# PAW3-NOMAG_Cheesecake-Blueberry-LSM6DSV_.net
KiCad netlist of a schematic drawn in EasyEDA Pro
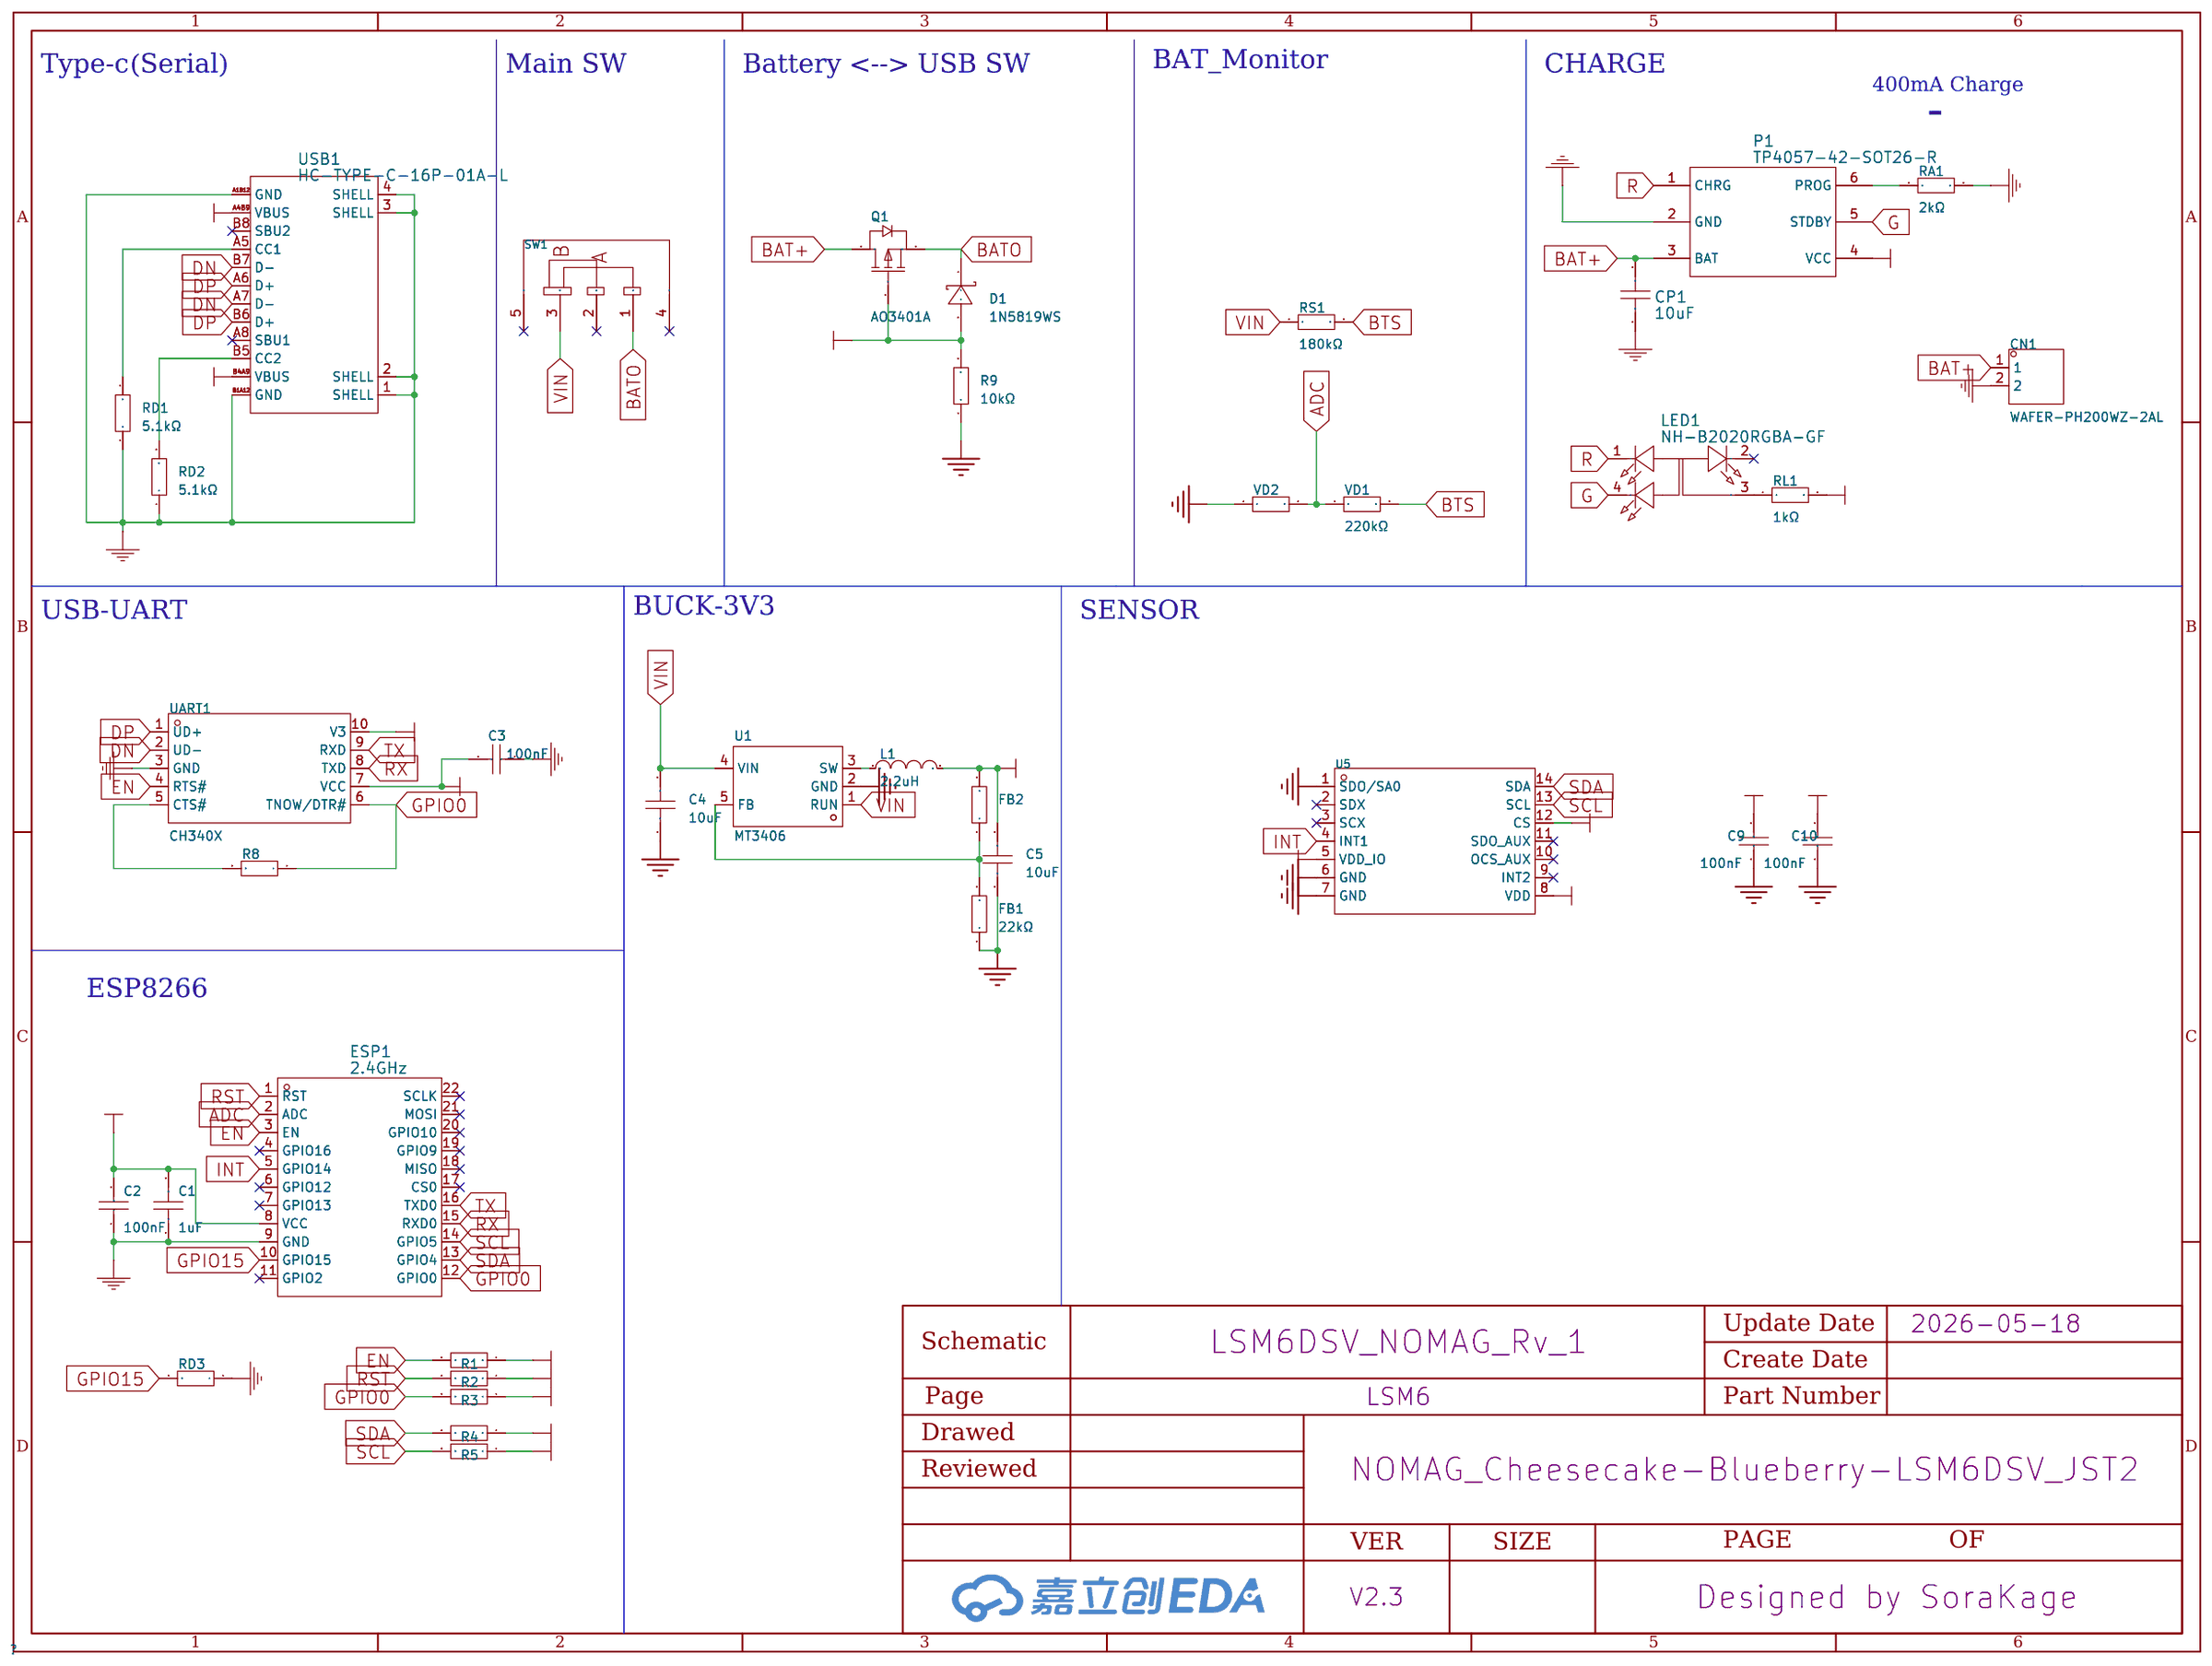
[diagram p0: schematic sheet]

(export (version "E")
  (design (tool "Eeschema 10.0.6"))
  (components
    (comp (ref "C1")
      (value "1uF")
      (footprint "easyedapro:C0402")
      (description "容值:1uF;精度:±10%;额定电压:25V;材质(温度系数):X5R;")
      (fields
        (field (name "Manufacturer Part") "CL05A105KA5NQNC")
        (field (name "Manufacturer") "SAMSUNG(三星)")
      )
      (libsource (lib "easyedapro") (part "CL05A105KA5NQNC"))
    )
    (comp (ref "C2")
      (value "100nF")
      (footprint "easyedapro:C0402")
      (description "容值:100nF;精度:±10%;额定电压:16V;材质(温度系数):X7R;")
      (fields
        (field (name "Manufacturer Part") "CL05B104KO5NNNC")
        (field (name "Manufacturer") "SAMSUNG(三星)")
      )
      (libsource (lib "easyedapro") (part "CL05B104KO5NNNC"))
    )
    (comp (ref "C3")
      (value "100nF")
      (footprint "easyedapro:C0402")
      (description "容值:100nF;精度:±10%;额定电压:16V;材质(温度系数):X7R;")
      (fields
        (field (name "Manufacturer Part") "CL05B104KO5NNNC")
        (field (name "Manufacturer") "SAMSUNG(三星)")
      )
      (libsource (lib "easyedapro") (part "CL05B104KO5NNNC"))
    )
    (comp (ref "C4")
      (value "10uF")
      (footprint "easyedapro:C0603")
      (description "容值:10uF;精度:±10%;额定电压:10V;材质(温度系数):X5R;")
      (fields
        (field (name "Manufacturer Part") "CL10A106KP8NNNC")
        (field (name "Manufacturer") "SAMSUNG(三星)")
      )
      (libsource (lib "easyedapro") (part "CL10A106KP8NNNC"))
    )
    (comp (ref "C5")
      (value "10uF")
      (footprint "easyedapro:C0603")
      (description "容值:10uF;精度:±10%;额定电压:10V;材质(温度系数):X5R;")
      (fields
        (field (name "Manufacturer Part") "CL10A106KP8NNNC")
        (field (name "Manufacturer") "SAMSUNG(三星)")
      )
      (libsource (lib "easyedapro") (part "CL10A106KP8NNNC"))
    )
    (comp (ref "C9")
      (value "100nF")
      (footprint "easyedapro:C0402")
      (description "容值:100nF;精度:±10%;额定电压:16V;材质(温度系数):X7R;")
      (fields
        (field (name "Manufacturer Part") "CL05B104KO5NNNC")
        (field (name "Manufacturer") "SAMSUNG(三星)")
      )
      (libsource (lib "easyedapro") (part "CL05B104KO5NNNC"))
    )
    (comp (ref "C10")
      (value "100nF")
      (footprint "easyedapro:C0402")
      (description "容值:100nF;精度:±10%;额定电压:16V;材质(温度系数):X7R;")
      (fields
        (field (name "Manufacturer Part") "CL05B104KO5NNNC")
        (field (name "Manufacturer") "SAMSUNG(三星)")
      )
      (libsource (lib "easyedapro") (part "CL05B104KO5NNNC"))
    )
    (comp (ref "CN1")
      (value "WAFER-PH200WZ-2AL")
      (footprint "easyedapro:CONN-TH_S2B-PH-K-S-LF-SN")
      (description "插针结构:1x2P;间距:2mm;安装方式:弯插;参考系列:PH;总PIN数:2P;排数:1;每排PIN数:2;行距:-;触头材质:黄铜;")
      (fields (field (name "Manufacturer") "HANBO(汉博)"))
      (libsource (lib "easyedapro") (part "S2B-PH-K-S(LF)(SN)"))
    )
    (comp (ref "CP1")
      (value "10uF")
      (footprint "easyedapro:C0603")
      (fields
        (field (name "Manufacturer Part") "CL10A106KP8NNNC")
        (field (name "Manufacturer") "SAMSUNG(三星)")
      )
      (libsource (lib "easyedapro") (part "10uF"))
    )
    (comp (ref "D1")
      (value "1N5819WS")
      (footprint "easyedapro:SOD-323_L1.8-W1.3-LS2.5-RD")
      (description "直流反向耐压(Vr):40V;平均整流电流(Io):1A;正向压降(Vf):600mV@1A;")
      (fields (field (name "Manufacturer") "Hottech(合科泰)"))
      (libsource (lib "easyedapro") (part "1N5819WS"))
    )
    (comp (ref "ESP1")
      (value "2.4GHz")
      (description "核心处理器:ESP8266芯片;频率:2.4GHz;天线形式:板载PCB天线;发射功率:16dBm;接收灵敏度:-90dBm;")
      (fields
        (field (name "Manufacturer Part") "ESP-12F(ESP8266MOD)")
        (field (name "Manufacturer") "Ai-Thinker(安信可)")
      )
      (libsource (lib "easyedapro") (part "ESP-12F(ESP8266MOD)"))
    )
    (comp (ref "FB1")
      (value "22kΩ")
      (footprint "easyedapro:R0402")
      (description "电阻类型:厚膜电阻;阻值:22kΩ;精度:±1%;功率:62.5mW;")
      (fields
        (field (name "Manufacturer Part") "0402WGF2202TCE")
        (field (name "Manufacturer") "UNI-ROYAL(厚声)")
      )
      (libsource (lib "easyedapro") (part "0402WGF2202TCE"))
    )
    (comp (ref "FB2")
      (value "100kΩ")
      (footprint "easyedapro:R0402")
      (fields
        (field (name "Manufacturer Part") "0402WGF1003TCE")
        (field (name "Manufacturer") "UNI-ROYAL(厚声)")
      )
      (libsource (lib "easyedapro") (part "0402WGF1003TCE"))
    )
    (comp (ref "L1")
      (value "2.2uH")
      (footprint "easyedapro:IND-SMD_L2.5-W2.0_YXMBL252010P")
      (description "类型:一体成型电感;电感值:2.2uH;精度:±20%;额定电流:2.1A;饱和电流(Isat):3A;")
      (fields (field (name "Manufacturer Part") "APH252010T2R2M") (field (name "Manufacturer") "APV(爱普微)"))
      (libsource (lib "easyedapro") (part "APH252010T2R2M"))
    )
    (comp (ref "LED1")
      (value "NH-B2020RGBA-GF")
      (footprint "easyedapro:LED-ARRAY-SMD_4P-L2.1-W2.1-TL_NH-B2020RGBA")
      (fields (field (name "Manufacturer") "国星光电"))
      (libsource (lib "easyedapro") (part "NH-B2020RGBA-GF"))
    )
    (comp (ref "P1")
      (value "TP4057-42-SOT26-R")
      (footprint "easyedapro:SOT-23-6_L2.9-W1.6-P0.95-LS2.8-BL")
      (fields (field (name "Manufacturer") "TOPPOWER(南京拓微)"))
      (libsource (lib "easyedapro") (part "TP4057"))
    )
    (comp (ref "Q1")
      (value "AO3401A")
      (footprint "easyedapro:SOT-23_L2.9-W1.3-P1.90-LS2.4-BR")
      (description "类型:P沟道;漏源电压(Vdss):30V;连续漏极电流(Id):4A;功率(Pd):1.4W;导通电阻(RDS(on)@Vgs,Id):44mΩ@10V,4.3A;")
      (fields (field (name "Manufacturer") "AOS"))
      (libsource (lib "easyedapro") (part "AO3401A"))
    )
    (comp (ref "R1")
      (value "4.7kΩ")
      (footprint "easyedapro:R0402")
      (fields
        (field (name "Manufacturer Part") "0402WGF4701TCE")
        (field (name "Manufacturer") "UNI-ROYAL(厚声)")
      )
      (libsource (lib "easyedapro") (part "0402WGF4701TCE"))
    )
    (comp (ref "R2")
      (value "4.7kΩ")
      (footprint "easyedapro:R0402")
      (fields
        (field (name "Manufacturer Part") "0402WGF4701TCE")
        (field (name "Manufacturer") "UNI-ROYAL(厚声)")
      )
      (libsource (lib "easyedapro") (part "0402WGF4701TCE"))
    )
    (comp (ref "R3")
      (value "4.7kΩ")
      (footprint "easyedapro:R0402")
      (fields
        (field (name "Manufacturer Part") "0402WGF4701TCE")
        (field (name "Manufacturer") "UNI-ROYAL(厚声)")
      )
      (libsource (lib "easyedapro") (part "0402WGF4701TCE"))
    )
    (comp (ref "R4")
      (value "4.7kΩ")
      (footprint "easyedapro:R0402")
      (fields
        (field (name "Manufacturer Part") "0402WGF4701TCE")
        (field (name "Manufacturer") "UNI-ROYAL(厚声)")
      )
      (libsource (lib "easyedapro") (part "0402WGF4701TCE"))
    )
    (comp (ref "R5")
      (value "4.7kΩ")
      (footprint "easyedapro:R0402")
      (fields
        (field (name "Manufacturer Part") "0402WGF4701TCE")
        (field (name "Manufacturer") "UNI-ROYAL(厚声)")
      )
      (libsource (lib "easyedapro") (part "0402WGF4701TCE"))
    )
    (comp (ref "R8")
      (value "4.7kΩ")
      (footprint "easyedapro:R0402")
      (fields
        (field (name "Manufacturer Part") "0402WGF4701TCE")
        (field (name "Manufacturer") "UNI-ROYAL(厚声)")
      )
      (libsource (lib "easyedapro") (part "0402WGF4701TCE"))
    )
    (comp (ref "R9")
      (value "10kΩ")
      (footprint "easyedapro:R0402")
      (description "电阻类型:厚膜电阻;阻值:10kΩ;精度:±1%;功率:62.5mW;")
      (fields
        (field (name "Manufacturer Part") "0402WGF1002TCE")
        (field (name "Manufacturer") "UNI-ROYAL(厚声)")
      )
      (libsource (lib "easyedapro") (part "0402WGF1002TCE"))
    )
    (comp (ref "RA1")
      (value "2kΩ")
      (footprint "easyedapro:R0402")
      (description "电阻类型:厚膜电阻;阻值:2kΩ;精度:±1%;功率:62.5mW;")
      (fields
        (field (name "Manufacturer Part") "0402WGF2001TCE")
        (field (name "Manufacturer") "UNI-ROYAL(厚声)")
      )
      (libsource (lib "easyedapro") (part "0402WGF2001TCE"))
    )
    (comp (ref "RD1")
      (value "5.1kΩ")
      (footprint "easyedapro:R0402")
      (description "电阻类型:厚膜电阻;阻值:5.1kΩ;精度:±1%;功率:62.5mW;")
      (fields
        (field (name "Manufacturer Part") "0402WGF5101TCE")
        (field (name "Manufacturer") "UNI-ROYAL(厚声)")
      )
      (libsource (lib "easyedapro") (part "0402WGF5101TCE"))
    )
    (comp (ref "RD2")
      (value "5.1kΩ")
      (footprint "easyedapro:R0402")
      (description "电阻类型:厚膜电阻;阻值:5.1kΩ;精度:±1%;功率:62.5mW;")
      (fields
        (field (name "Manufacturer Part") "0402WGF5101TCE")
        (field (name "Manufacturer") "UNI-ROYAL(厚声)")
      )
      (libsource (lib "easyedapro") (part "0402WGF5101TCE"))
    )
    (comp (ref "RD3")
      (value "4.7kΩ")
      (footprint "easyedapro:R0402")
      (fields
        (field (name "Manufacturer Part") "0402WGF4701TCE")
        (field (name "Manufacturer") "UNI-ROYAL(厚声)")
      )
      (libsource (lib "easyedapro") (part "0402WGF4701TCE"))
    )
    (comp (ref "RL1")
      (value "1kΩ")
      (footprint "easyedapro:R0402")
      (description "电阻类型:厚膜电阻;阻值:1kΩ;精度:±1%;功率:62.5mW;")
      (fields
        (field (name "Manufacturer Part") "0402WGF1001TCE")
        (field (name "Manufacturer") "UNI-ROYAL(厚声)")
      )
      (libsource (lib "easyedapro") (part "0402WGF1001TCE"))
    )
    (comp (ref "RS1")
      (value "180kΩ")
      (footprint "easyedapro:R0402")
      (description "阻值:180kΩ;精度:±1%;功率:62.5mW;温度系数:±100ppm/°C;电阻类型:厚膜电阻;")
      (fields
        (field (name "Manufacturer Part") "0402WGF1803TCE")
        (field (name "Manufacturer") "UNI-ROYAL(厚声)")
      )
      (libsource (lib "easyedapro") (part "0402WGF1803TCE"))
    )
    (comp (ref "SW1")
      (value "K3-1270S-F2")
      (footprint "easyedapro:SW-TH_K3-1270S-F2")
      (fields (field (name "Manufacturer") "韩国韩荣"))
      (libsource (lib "easyedapro") (part "K3-1270S-F2"))
    )
    (comp (ref "U1")
      (value "MT3406")
      (footprint "easyedapro:SOT-23-5_L3.0-W1.7-P0.95-LS2.8-BR")
      (description "功能类型:降压型;同步整流:-;输出通道数:-;拓扑结构:-;输入电压:-;输出电流(最大值):-;开关频率:-;")
      (fields (field (name "Manufacturer") "西安航天民芯"))
      (libsource (lib "easyedapro") (part "M3406"))
    )
    (comp (ref "U5")
      (value "LSM6DSVQTR")
      (footprint "easyedapro:LGA-14_L3.0-W2.5-P0.50-TL")
      (fields (field (name "Manufacturer") "ST(意法半导体)"))
      (libsource (lib "easyedapro") (part "LSM6DSVQTR"))
    )
    (comp (ref "UART1")
      (value "CH340X")
      (footprint "easyedapro:MSOP-10_L3.0-W3.0-P0.50-LS5.0-BL")
      (fields (field (name "Manufacturer") "WCH(南京沁恒)"))
      (libsource (lib "easyedapro") (part "CH340X"))
    )
    (comp (ref "USB1")
      (value "HC-TYPE-C-16P-01A-L")
      (footprint "easyedapro:USB-C-SMD_G-SWITCH_GT-USB-7010EN")
      (fields (field (name "Manufacturer") "HCTL(华灿天禄)"))
      (libsource (lib "easyedapro") (part "HC-TYPE-C-16P-01A-L"))
    )
    (comp (ref "VD1")
      (value "220kΩ")
      (footprint "easyedapro:R0402")
      (description "电阻类型:厚膜电阻;阻值:220kΩ;精度:±1%;功率:62.5mW;")
      (fields
        (field (name "Manufacturer Part") "0402WGF2203TCE")
        (field (name "Manufacturer") "UNI-ROYAL(厚声)")
      )
      (libsource (lib "easyedapro") (part "0402WGF2203TCE"))
    )
    (comp (ref "VD2")
      (value "100kΩ")
      (footprint "easyedapro:R0402")
      (fields
        (field (name "Manufacturer Part") "0402WGF1003TCE")
        (field (name "Manufacturer") "UNI-ROYAL(厚声)")
      )
      (libsource (lib "easyedapro") (part "0402WGF1003TCE"))
    )
  )
  (nets
    (net (code "1") (name "+5V") (class "Default")
      (node (ref "D1") (pin "2") (pinfunction "A_2") (pintype "unspecified"))
      (node (ref "P1") (pin "4") (pinfunction "VCC_4") (pintype "unspecified"))
      (node (ref "Q1") (pin "1") (pinfunction "G_1") (pintype "input"))
      (node (ref "R9") (pin "2") (pinfunction "2_2") (pintype "input"))
      (node (ref "RL1") (pin "2") (pinfunction "2_2") (pintype "input"))
      (node (ref "USB1") (pin "A4B9") (pinfunction "VBUS_A4B9") (pintype "unspecified"))
      (node (ref "USB1") (pin "B4A9") (pinfunction "VBUS_B4A9") (pintype "unspecified"))
    )
    (net (code "2") (name "3V3") (class "Default")
      (node (ref "C1") (pin "2") (pinfunction "2_2") (pintype "unspecified"))
      (node (ref "C10") (pin "1") (pinfunction "1_1") (pintype "input"))
      (node (ref "C2") (pin "2") (pinfunction "2_2") (pintype "input"))
      (node (ref "C3") (pin "2") (pinfunction "2_2") (pintype "input"))
      (node (ref "C5") (pin "2") (pinfunction "2_2") (pintype "unspecified"))
      (node (ref "C9") (pin "1") (pinfunction "1_1") (pintype "input"))
      (node (ref "ESP1") (pin "8") (pinfunction "VCC_8") (pintype "input"))
      (node (ref "FB2") (pin "2") (pinfunction "2_2") (pintype "input"))
      (node (ref "L1") (pin "2") (pinfunction "2_2") (pintype "unspecified"))
      (node (ref "R1") (pin "1") (pinfunction "1_1") (pintype "input"))
      (node (ref "R2") (pin "1") (pinfunction "1_1") (pintype "input"))
      (node (ref "R3") (pin "1") (pinfunction "1_1") (pintype "input"))
      (node (ref "R4") (pin "1") (pinfunction "1_1") (pintype "input"))
      (node (ref "R5") (pin "1") (pinfunction "1_1") (pintype "input"))
      (node (ref "U5") (pin "12") (pinfunction "CS_12") (pintype "unspecified"))
      (node (ref "U5") (pin "5") (pinfunction "VDD_IO_5") (pintype "unspecified"))
      (node (ref "U5") (pin "8") (pinfunction "VDD_8") (pintype "unspecified"))
      (node (ref "UART1") (pin "10") (pinfunction "V3_10") (pintype "unspecified"))
      (node (ref "UART1") (pin "7") (pinfunction "VCC_7") (pintype "unspecified"))
    )
    (net (code "3") (name "ADC") (class "Default")
      (node (ref "ESP1") (pin "2") (pinfunction "ADC_2") (pintype "input"))
      (node (ref "VD1") (pin "1") (pinfunction "1_1") (pintype "input"))
      (node (ref "VD2") (pin "2") (pinfunction "2_2") (pintype "input"))
    )
    (net (code "4") (name "BAT+") (class "Default")
      (node (ref "CN1") (pin "1") (pinfunction "1_1") (pintype "unspecified"))
      (node (ref "CP1") (pin "2") (pinfunction "2_2") (pintype "input"))
      (node (ref "P1") (pin "3") (pinfunction "BAT_3") (pintype "unspecified"))
      (node (ref "Q1") (pin "3") (pinfunction "D_3") (pintype "input"))
    )
    (net (code "5") (name "BATO") (class "Default")
      (node (ref "D1") (pin "1") (pinfunction "K_1") (pintype "unspecified"))
      (node (ref "Q1") (pin "2") (pinfunction "S_2") (pintype "input"))
      (node (ref "SW1") (pin "1") (pinfunction "1_1") (pintype "input"))
    )
    (net (code "6") (name "BTS") (class "Default")
      (node (ref "RS1") (pin "2") (pinfunction "2_2") (pintype "input"))
      (node (ref "VD1") (pin "2") (pinfunction "2_2") (pintype "input"))
    )
    (net (code "7") (name "DN") (class "Default")
      (node (ref "UART1") (pin "2") (pinfunction "UD-_2") (pintype "unspecified"))
      (node (ref "USB1") (pin "A7") (pinfunction "D-_A7") (pintype "unspecified"))
      (node (ref "USB1") (pin "B7") (pinfunction "D-_B7") (pintype "unspecified"))
    )
    (net (code "8") (name "DP") (class "Default")
      (node (ref "UART1") (pin "1") (pinfunction "UD+_1") (pintype "unspecified"))
      (node (ref "USB1") (pin "A6") (pinfunction "D+_A6") (pintype "unspecified"))
      (node (ref "USB1") (pin "B6") (pinfunction "D+_B6") (pintype "unspecified"))
    )
    (net (code "9") (name "EN") (class "Default")
      (node (ref "ESP1") (pin "3") (pinfunction "EN_3") (pintype "input"))
      (node (ref "R1") (pin "2") (pinfunction "2_2") (pintype "input"))
      (node (ref "UART1") (pin "4") (pinfunction "RTS#_4") (pintype "unspecified"))
    )
    (net (code "10") (name "G") (class "Default")
      (node (ref "LED1") (pin "4") (pinfunction "-_4") (pintype "unspecified"))
      (node (ref "P1") (pin "5") (pinfunction "STDBY_5") (pintype "unspecified"))
    )
    (net (code "11") (name "GND") (class "Default")
      (node (ref "C1") (pin "1") (pinfunction "1_1") (pintype "unspecified"))
      (node (ref "C10") (pin "2") (pinfunction "2_2") (pintype "input"))
      (node (ref "C2") (pin "1") (pinfunction "1_1") (pintype "input"))
      (node (ref "C3") (pin "1") (pinfunction "1_1") (pintype "input"))
      (node (ref "C4") (pin "1") (pinfunction "1_1") (pintype "unspecified"))
      (node (ref "C5") (pin "1") (pinfunction "1_1") (pintype "unspecified"))
      (node (ref "C9") (pin "2") (pinfunction "2_2") (pintype "input"))
      (node (ref "CN1") (pin "2") (pinfunction "2_2") (pintype "unspecified"))
      (node (ref "CP1") (pin "1") (pinfunction "1_1") (pintype "input"))
      (node (ref "ESP1") (pin "9") (pinfunction "GND_9") (pintype "input"))
      (node (ref "FB1") (pin "1") (pinfunction "1_1") (pintype "input"))
      (node (ref "P1") (pin "2") (pinfunction "GND_2") (pintype "unspecified"))
      (node (ref "R9") (pin "1") (pinfunction "1_1") (pintype "input"))
      (node (ref "RA1") (pin "2") (pinfunction "2_2") (pintype "input"))
      (node (ref "RD1") (pin "1") (pinfunction "1_1") (pintype "input"))
      (node (ref "RD2") (pin "1") (pinfunction "1_1") (pintype "input"))
      (node (ref "RD3") (pin "1") (pinfunction "1_1") (pintype "input"))
      (node (ref "U1") (pin "2") (pinfunction "GND_2") (pintype "input"))
      (node (ref "U5") (pin "1") (pinfunction "SDO/SA0_1") (pintype "unspecified"))
      (node (ref "U5") (pin "6") (pinfunction "GND_6") (pintype "unspecified"))
      (node (ref "U5") (pin "7") (pinfunction "GND_7") (pintype "unspecified"))
      (node (ref "UART1") (pin "3") (pinfunction "GND_3") (pintype "unspecified"))
      (node (ref "USB1") (pin "1") (pinfunction "SHELL_1") (pintype "unspecified"))
      (node (ref "USB1") (pin "2") (pinfunction "SHELL_2") (pintype "unspecified"))
      (node (ref "USB1") (pin "3") (pinfunction "SHELL_3") (pintype "unspecified"))
      (node (ref "USB1") (pin "4") (pinfunction "SHELL_4") (pintype "unspecified"))
      (node (ref "USB1") (pin "A1B12") (pinfunction "GND_A1B12") (pintype "unspecified"))
      (node (ref "USB1") (pin "B1A12") (pinfunction "GND_B1A12") (pintype "unspecified"))
      (node (ref "VD2") (pin "1") (pinfunction "1_1") (pintype "input"))
    )
    (net (code "12") (name "GPIO0") (class "Default")
      (node (ref "ESP1") (pin "12") (pinfunction "GPIO0_12") (pintype "input"))
      (node (ref "R3") (pin "2") (pinfunction "2_2") (pintype "input"))
      (node (ref "R8") (pin "1") (pinfunction "1_1") (pintype "input"))
      (node (ref "UART1") (pin "6") (pinfunction "TNOW/DTR#_6") (pintype "unspecified"))
    )
    (net (code "13") (name "GPIO15") (class "Default")
      (node (ref "ESP1") (pin "10") (pinfunction "GPIO15_10") (pintype "input"))
      (node (ref "RD3") (pin "2") (pinfunction "2_2") (pintype "input"))
    )
    (net (code "14") (name "INT") (class "Default")
      (node (ref "ESP1") (pin "5") (pinfunction "GPIO14_5") (pintype "input"))
      (node (ref "U5") (pin "4") (pinfunction "INT1_4") (pintype "unspecified"))
    )
    (net (code "15") (name "Net-(LED1-+)") (class "Default")
      (node (ref "LED1") (pin "3") (pinfunction "+_3") (pintype "unspecified"))
      (node (ref "RL1") (pin "1") (pinfunction "1_1") (pintype "input"))
    )
    (net (code "16") (name "Net-(P1-PROG)") (class "Default")
      (node (ref "P1") (pin "6") (pinfunction "PROG_6") (pintype "unspecified"))
      (node (ref "RA1") (pin "1") (pinfunction "1_1") (pintype "input"))
    )
    (net (code "17") (name "Net-(U1-FB)") (class "Default")
      (node (ref "FB1") (pin "2") (pinfunction "2_2") (pintype "input"))
      (node (ref "FB2") (pin "1") (pinfunction "1_1") (pintype "input"))
      (node (ref "U1") (pin "5") (pinfunction "FB_5") (pintype "input"))
    )
    (net (code "18") (name "Net-(U1-SW)") (class "Default")
      (node (ref "L1") (pin "1") (pinfunction "1_1") (pintype "unspecified"))
      (node (ref "U1") (pin "3") (pinfunction "SW_3") (pintype "input"))
    )
    (net (code "19") (name "Net-(UART1-CTS#)") (class "Default")
      (node (ref "R8") (pin "2") (pinfunction "2_2") (pintype "input"))
      (node (ref "UART1") (pin "5") (pinfunction "CTS#_5") (pintype "unspecified"))
    )
    (net (code "20") (name "Net-(USB1-CC1)") (class "Default")
      (node (ref "RD1") (pin "2") (pinfunction "2_2") (pintype "input"))
      (node (ref "USB1") (pin "A5") (pinfunction "CC1_A5") (pintype "unspecified"))
    )
    (net (code "21") (name "Net-(USB1-CC2)") (class "Default")
      (node (ref "RD2") (pin "2") (pinfunction "2_2") (pintype "input"))
      (node (ref "USB1") (pin "B5") (pinfunction "CC2_B5") (pintype "unspecified"))
    )
    (net (code "22") (name "R") (class "Default")
      (node (ref "LED1") (pin "1") (pinfunction "-_1") (pintype "unspecified"))
      (node (ref "P1") (pin "1") (pinfunction "CHRG_1") (pintype "unspecified"))
    )
    (net (code "23") (name "RST") (class "Default")
      (node (ref "ESP1") (pin "1") (pinfunction "RST_1") (pintype "input"))
      (node (ref "R2") (pin "2") (pinfunction "2_2") (pintype "input"))
    )
    (net (code "24") (name "RX") (class "Default")
      (node (ref "ESP1") (pin "15") (pinfunction "RXD0_15") (pintype "input"))
      (node (ref "UART1") (pin "8") (pinfunction "TXD_8") (pintype "unspecified"))
    )
    (net (code "25") (name "SCL") (class "Default")
      (node (ref "ESP1") (pin "14") (pinfunction "GPIO5_14") (pintype "input"))
      (node (ref "R5") (pin "2") (pinfunction "2_2") (pintype "input"))
      (node (ref "U5") (pin "13") (pinfunction "SCL_13") (pintype "unspecified"))
    )
    (net (code "26") (name "SDA") (class "Default")
      (node (ref "ESP1") (pin "13") (pinfunction "GPIO4_13") (pintype "input"))
      (node (ref "R4") (pin "2") (pinfunction "2_2") (pintype "input"))
      (node (ref "U5") (pin "14") (pinfunction "SDA_14") (pintype "unspecified"))
    )
    (net (code "27") (name "TX") (class "Default")
      (node (ref "ESP1") (pin "16") (pinfunction "TXD0_16") (pintype "input"))
      (node (ref "UART1") (pin "9") (pinfunction "RXD_9") (pintype "unspecified"))
    )
    (net (code "28") (name "VIN") (class "Default")
      (node (ref "C4") (pin "2") (pinfunction "2_2") (pintype "unspecified"))
      (node (ref "RS1") (pin "1") (pinfunction "1_1") (pintype "input"))
      (node (ref "SW1") (pin "3") (pinfunction "3_3") (pintype "input"))
      (node (ref "U1") (pin "1") (pinfunction "RUN_1") (pintype "input"))
      (node (ref "U1") (pin "4") (pinfunction "VIN_4") (pintype "input"))
    )
    (net (code "29") (name "unconnected-(ESP1-CS0-Pad17)") (class "Default")
      (node (ref "ESP1") (pin "17") (pinfunction "CS0_17") (pintype "input+no_connect"))
    )
    (net (code "30") (name "unconnected-(ESP1-GPIO2-Pad11)") (class "Default")
      (node (ref "ESP1") (pin "11") (pinfunction "GPIO2_11") (pintype "input+no_connect"))
    )
    (net (code "31") (name "unconnected-(ESP1-GPIO9-Pad19)") (class "Default")
      (node (ref "ESP1") (pin "19") (pinfunction "GPIO9_19") (pintype "input+no_connect"))
    )
    (net (code "32") (name "unconnected-(ESP1-GPIO10-Pad20)") (class "Default")
      (node (ref "ESP1") (pin "20") (pinfunction "GPIO10_20") (pintype "input+no_connect"))
    )
    (net (code "33") (name "unconnected-(ESP1-GPIO12-Pad6)") (class "Default")
      (node (ref "ESP1") (pin "6") (pinfunction "GPIO12_6") (pintype "input+no_connect"))
    )
    (net (code "34") (name "unconnected-(ESP1-GPIO13-Pad7)") (class "Default")
      (node (ref "ESP1") (pin "7") (pinfunction "GPIO13_7") (pintype "input+no_connect"))
    )
    (net (code "35") (name "unconnected-(ESP1-GPIO16-Pad4)") (class "Default")
      (node (ref "ESP1") (pin "4") (pinfunction "GPIO16_4") (pintype "input+no_connect"))
    )
    (net (code "36") (name "unconnected-(ESP1-MISO-Pad18)") (class "Default")
      (node (ref "ESP1") (pin "18") (pinfunction "MISO_18") (pintype "input+no_connect"))
    )
    (net (code "37") (name "unconnected-(ESP1-MOSI-Pad21)") (class "Default")
      (node (ref "ESP1") (pin "21") (pinfunction "MOSI_21") (pintype "input+no_connect"))
    )
    (net (code "38") (name "unconnected-(ESP1-SCLK-Pad22)") (class "Default")
      (node (ref "ESP1") (pin "22") (pinfunction "SCLK_22") (pintype "input+no_connect"))
    )
    (net (code "39") (name "unconnected-(LED1---Pad2)") (class "Default")
      (node (ref "LED1") (pin "2") (pinfunction "-_2") (pintype "unspecified+no_connect"))
    )
    (net (code "40") (name "unconnected-(SW1-Pad2)") (class "Default")
      (node (ref "SW1") (pin "2") (pinfunction "2_2") (pintype "input+no_connect"))
    )
    (net (code "41") (name "unconnected-(SW1-Pad4)") (class "Default")
      (node (ref "SW1") (pin "4") (pinfunction "4_4") (pintype "input+no_connect"))
    )
    (net (code "42") (name "unconnected-(SW1-Pad5)") (class "Default")
      (node (ref "SW1") (pin "5") (pinfunction "5_5") (pintype "input+no_connect"))
    )
    (net (code "43") (name "unconnected-(U5-INT2-Pad9)") (class "Default")
      (node (ref "U5") (pin "9") (pinfunction "INT2_9") (pintype "unspecified+no_connect"))
    )
    (net (code "44") (name "unconnected-(U5-OCS_AUX-Pad10)") (class "Default")
      (node (ref "U5") (pin "10") (pinfunction "OCS_AUX_10") (pintype "unspecified+no_connect"))
    )
    (net (code "45") (name "unconnected-(U5-SCX-Pad3)") (class "Default")
      (node (ref "U5") (pin "3") (pinfunction "SCX_3") (pintype "unspecified+no_connect"))
    )
    (net (code "46") (name "unconnected-(U5-SDO_AUX-Pad11)") (class "Default")
      (node (ref "U5") (pin "11") (pinfunction "SDO_AUX_11") (pintype "unspecified+no_connect"))
    )
    (net (code "47") (name "unconnected-(U5-SDX-Pad2)") (class "Default")
      (node (ref "U5") (pin "2") (pinfunction "SDX_2") (pintype "unspecified+no_connect"))
    )
    (net (code "48") (name "unconnected-(USB1-SBU1-PadA8)") (class "Default")
      (node (ref "USB1") (pin "A8") (pinfunction "SBU1_A8") (pintype "unspecified+no_connect"))
    )
    (net (code "49") (name "unconnected-(USB1-SBU2-PadB8)") (class "Default")
      (node (ref "USB1") (pin "B8") (pinfunction "SBU2_B8") (pintype "unspecified+no_connect"))
    )
  )
)
